# version1_1.net
KiCad netlist of a schematic drawn in EAGLE
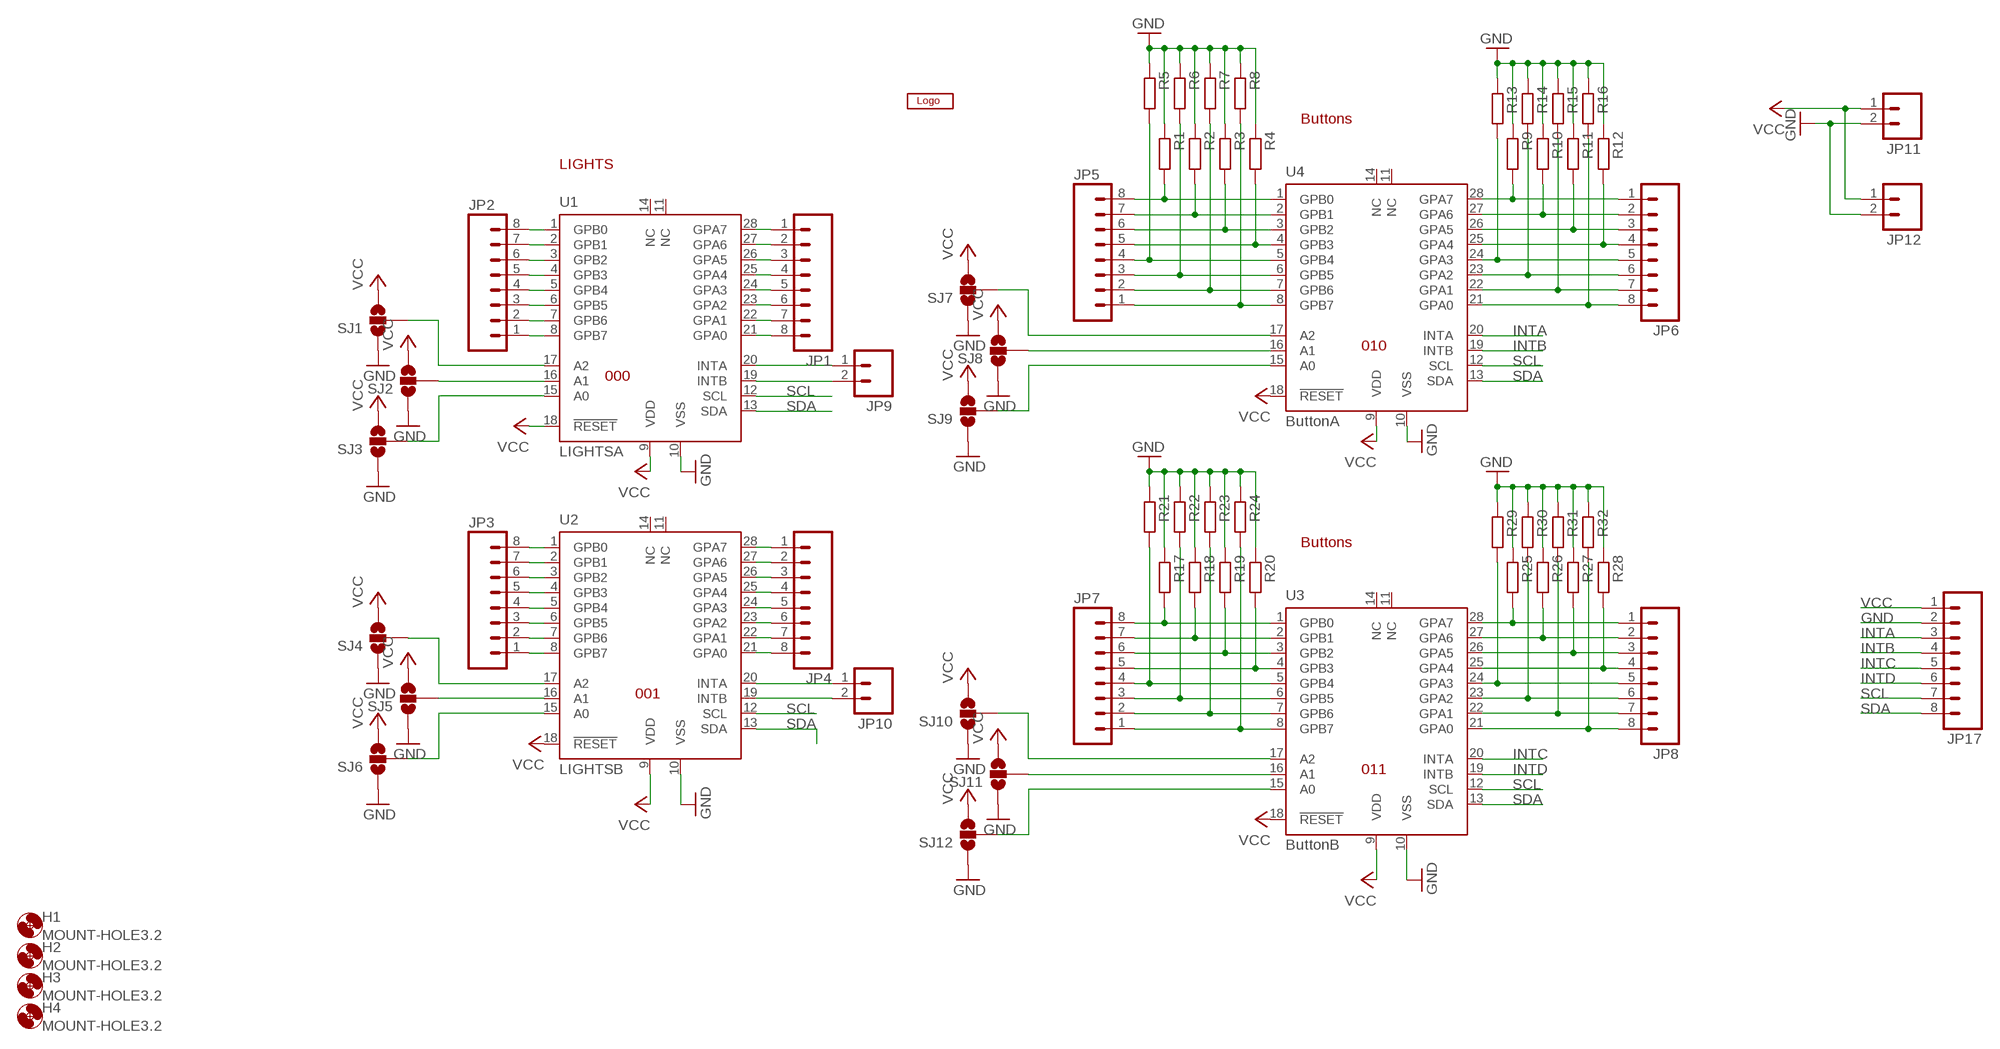
[diagram p0: schematic, sheet 1]

(export (version "E")
  (design (tool "Eeschema 10.0.6"))
  (components
    (comp (ref "H1")
      (value "MOUNT-HOLE3.2")
      (footprint "eagle-import:3,2")
      (libsource (lib "eagle-import") (part "MOUNT-HOLE3.2"))
    )
    (comp (ref "H2")
      (value "MOUNT-HOLE3.2")
      (footprint "eagle-import:3,2")
      (libsource (lib "eagle-import") (part "MOUNT-HOLE3.2"))
    )
    (comp (ref "H3")
      (value "MOUNT-HOLE3.2")
      (footprint "eagle-import:3,2")
      (libsource (lib "eagle-import") (part "MOUNT-HOLE3.2"))
    )
    (comp (ref "H4")
      (value "MOUNT-HOLE3.2")
      (footprint "eagle-import:3,2")
      (libsource (lib "eagle-import") (part "MOUNT-HOLE3.2"))
    )
    (comp (ref "JP1")
      (value "M08LOCK")
      (footprint "eagle-import:1X08_LOCK")
      (libsource (lib "eagle-import") (part "M08LOCK"))
    )
    (comp (ref "JP2")
      (value "M08LOCK")
      (footprint "eagle-import:1X08_LOCK")
      (libsource (lib "eagle-import") (part "M08LOCK"))
    )
    (comp (ref "JP3")
      (value "M08LOCK")
      (footprint "eagle-import:1X08_LOCK")
      (libsource (lib "eagle-import") (part "M08LOCK"))
    )
    (comp (ref "JP4")
      (value "M08LOCK")
      (footprint "eagle-import:1X08_LOCK")
      (libsource (lib "eagle-import") (part "M08LOCK"))
    )
    (comp (ref "JP5")
      (value "M08LOCK")
      (footprint "eagle-import:1X08_LOCK")
      (libsource (lib "eagle-import") (part "M08LOCK"))
    )
    (comp (ref "JP6")
      (value "M08LOCK")
      (footprint "eagle-import:1X08_LOCK")
      (libsource (lib "eagle-import") (part "M08LOCK"))
    )
    (comp (ref "JP7")
      (value "M08LOCK")
      (footprint "eagle-import:1X08_LOCK")
      (libsource (lib "eagle-import") (part "M08LOCK"))
    )
    (comp (ref "JP8")
      (value "M08LOCK")
      (footprint "eagle-import:1X08_LOCK")
      (libsource (lib "eagle-import") (part "M08LOCK"))
    )
    (comp (ref "JP9")
      (value "M021X02_NO_SILK")
      (footprint "eagle-import:1X02_NO_SILK")
      (libsource (lib "eagle-import") (part "M021X02_NO_SILK"))
    )
    (comp (ref "JP10")
      (value "M021X02_NO_SILK")
      (footprint "eagle-import:1X02_NO_SILK")
      (libsource (lib "eagle-import") (part "M021X02_NO_SILK"))
    )
    (comp (ref "JP11")
      (value "M021X02_NO_SILK")
      (footprint "eagle-import:1X02_NO_SILK")
      (libsource (lib "eagle-import") (part "M021X02_NO_SILK"))
    )
    (comp (ref "JP12")
      (value "M021X02_NO_SILK")
      (footprint "eagle-import:1X02_NO_SILK")
      (libsource (lib "eagle-import") (part "M021X02_NO_SILK"))
    )
    (comp (ref "JP17")
      (value "M08LOCK")
      (footprint "eagle-import:1X08_LOCK")
      (libsource (lib "eagle-import") (part "M08LOCK"))
    )
    (comp (ref "R1")
      (value "R-EU_R0805")
      (footprint "eagle-import:R0805")
      (libsource (lib "eagle-import") (part "R-EU_R0805"))
    )
    (comp (ref "R2")
      (value "R-EU_R0805")
      (footprint "eagle-import:R0805")
      (libsource (lib "eagle-import") (part "R-EU_R0805"))
    )
    (comp (ref "R3")
      (value "R-EU_R0805")
      (footprint "eagle-import:R0805")
      (libsource (lib "eagle-import") (part "R-EU_R0805"))
    )
    (comp (ref "R4")
      (value "R-EU_R0805")
      (footprint "eagle-import:R0805")
      (libsource (lib "eagle-import") (part "R-EU_R0805"))
    )
    (comp (ref "R5")
      (value "R-EU_R0805")
      (footprint "eagle-import:R0805")
      (libsource (lib "eagle-import") (part "R-EU_R0805"))
    )
    (comp (ref "R6")
      (value "R-EU_R0805")
      (footprint "eagle-import:R0805")
      (libsource (lib "eagle-import") (part "R-EU_R0805"))
    )
    (comp (ref "R7")
      (value "R-EU_R0805")
      (footprint "eagle-import:R0805")
      (libsource (lib "eagle-import") (part "R-EU_R0805"))
    )
    (comp (ref "R8")
      (value "R-EU_R0805")
      (footprint "eagle-import:R0805")
      (libsource (lib "eagle-import") (part "R-EU_R0805"))
    )
    (comp (ref "R9")
      (value "R-EU_R0805")
      (footprint "eagle-import:R0805")
      (libsource (lib "eagle-import") (part "R-EU_R0805"))
    )
    (comp (ref "R10")
      (value "R-EU_R0805")
      (footprint "eagle-import:R0805")
      (libsource (lib "eagle-import") (part "R-EU_R0805"))
    )
    (comp (ref "R11")
      (value "R-EU_R0805")
      (footprint "eagle-import:R0805")
      (libsource (lib "eagle-import") (part "R-EU_R0805"))
    )
    (comp (ref "R12")
      (value "R-EU_R0805")
      (footprint "eagle-import:R0805")
      (libsource (lib "eagle-import") (part "R-EU_R0805"))
    )
    (comp (ref "R13")
      (value "R-EU_R0805")
      (footprint "eagle-import:R0805")
      (libsource (lib "eagle-import") (part "R-EU_R0805"))
    )
    (comp (ref "R14")
      (value "R-EU_R0805")
      (footprint "eagle-import:R0805")
      (libsource (lib "eagle-import") (part "R-EU_R0805"))
    )
    (comp (ref "R15")
      (value "R-EU_R0805")
      (footprint "eagle-import:R0805")
      (libsource (lib "eagle-import") (part "R-EU_R0805"))
    )
    (comp (ref "R16")
      (value "R-EU_R0805")
      (footprint "eagle-import:R0805")
      (libsource (lib "eagle-import") (part "R-EU_R0805"))
    )
    (comp (ref "R17")
      (value "R-EU_R0805")
      (footprint "eagle-import:R0805")
      (libsource (lib "eagle-import") (part "R-EU_R0805"))
    )
    (comp (ref "R18")
      (value "R-EU_R0805")
      (footprint "eagle-import:R0805")
      (libsource (lib "eagle-import") (part "R-EU_R0805"))
    )
    (comp (ref "R19")
      (value "R-EU_R0805")
      (footprint "eagle-import:R0805")
      (libsource (lib "eagle-import") (part "R-EU_R0805"))
    )
    (comp (ref "R20")
      (value "R-EU_R0805")
      (footprint "eagle-import:R0805")
      (libsource (lib "eagle-import") (part "R-EU_R0805"))
    )
    (comp (ref "R21")
      (value "R-EU_R0805")
      (footprint "eagle-import:R0805")
      (libsource (lib "eagle-import") (part "R-EU_R0805"))
    )
    (comp (ref "R22")
      (value "R-EU_R0805")
      (footprint "eagle-import:R0805")
      (libsource (lib "eagle-import") (part "R-EU_R0805"))
    )
    (comp (ref "R23")
      (value "R-EU_R0805")
      (footprint "eagle-import:R0805")
      (libsource (lib "eagle-import") (part "R-EU_R0805"))
    )
    (comp (ref "R24")
      (value "R-EU_R0805")
      (footprint "eagle-import:R0805")
      (libsource (lib "eagle-import") (part "R-EU_R0805"))
    )
    (comp (ref "R25")
      (value "R-EU_R0805")
      (footprint "eagle-import:R0805")
      (libsource (lib "eagle-import") (part "R-EU_R0805"))
    )
    (comp (ref "R26")
      (value "R-EU_R0805")
      (footprint "eagle-import:R0805")
      (libsource (lib "eagle-import") (part "R-EU_R0805"))
    )
    (comp (ref "R27")
      (value "R-EU_R0805")
      (footprint "eagle-import:R0805")
      (libsource (lib "eagle-import") (part "R-EU_R0805"))
    )
    (comp (ref "R28")
      (value "R-EU_R0805")
      (footprint "eagle-import:R0805")
      (libsource (lib "eagle-import") (part "R-EU_R0805"))
    )
    (comp (ref "R29")
      (value "R-EU_R0805")
      (footprint "eagle-import:R0805")
      (libsource (lib "eagle-import") (part "R-EU_R0805"))
    )
    (comp (ref "R30")
      (value "R-EU_R0805")
      (footprint "eagle-import:R0805")
      (libsource (lib "eagle-import") (part "R-EU_R0805"))
    )
    (comp (ref "R31")
      (value "R-EU_R0805")
      (footprint "eagle-import:R0805")
      (libsource (lib "eagle-import") (part "R-EU_R0805"))
    )
    (comp (ref "R32")
      (value "R-EU_R0805")
      (footprint "eagle-import:R0805")
      (libsource (lib "eagle-import") (part "R-EU_R0805"))
    )
    (comp (ref "SJ1")
      (value "SOLDERJUMPER_2WAY-OLDS")
      (footprint "eagle-import:SJ_3")
      (libsource (lib "eagle-import") (part "SOLDERJUMPER_2WAY-OLDS"))
    )
    (comp (ref "SJ2")
      (value "SOLDERJUMPER_2WAY-OLDS")
      (footprint "eagle-import:SJ_3")
      (libsource (lib "eagle-import") (part "SOLDERJUMPER_2WAY-OLDS"))
    )
    (comp (ref "SJ3")
      (value "SOLDERJUMPER_2WAY-OLDS")
      (footprint "eagle-import:SJ_3")
      (libsource (lib "eagle-import") (part "SOLDERJUMPER_2WAY-OLDS"))
    )
    (comp (ref "SJ4")
      (value "SOLDERJUMPER_2WAY-OLDS")
      (footprint "eagle-import:SJ_3")
      (libsource (lib "eagle-import") (part "SOLDERJUMPER_2WAY-OLDS"))
    )
    (comp (ref "SJ5")
      (value "SOLDERJUMPER_2WAY-OLDS")
      (footprint "eagle-import:SJ_3")
      (libsource (lib "eagle-import") (part "SOLDERJUMPER_2WAY-OLDS"))
    )
    (comp (ref "SJ6")
      (value "SOLDERJUMPER_2WAY-OLDS")
      (footprint "eagle-import:SJ_3")
      (libsource (lib "eagle-import") (part "SOLDERJUMPER_2WAY-OLDS"))
    )
    (comp (ref "SJ7")
      (value "SOLDERJUMPER_2WAY-OLDS")
      (footprint "eagle-import:SJ_3")
      (libsource (lib "eagle-import") (part "SOLDERJUMPER_2WAY-OLDS"))
    )
    (comp (ref "SJ8")
      (value "SOLDERJUMPER_2WAY-OLDS")
      (footprint "eagle-import:SJ_3")
      (libsource (lib "eagle-import") (part "SOLDERJUMPER_2WAY-OLDS"))
    )
    (comp (ref "SJ9")
      (value "SOLDERJUMPER_2WAY-OLDS")
      (footprint "eagle-import:SJ_3")
      (libsource (lib "eagle-import") (part "SOLDERJUMPER_2WAY-OLDS"))
    )
    (comp (ref "SJ10")
      (value "SOLDERJUMPER_2WAY-OLDS")
      (footprint "eagle-import:SJ_3")
      (libsource (lib "eagle-import") (part "SOLDERJUMPER_2WAY-OLDS"))
    )
    (comp (ref "SJ11")
      (value "SOLDERJUMPER_2WAY-OLDS")
      (footprint "eagle-import:SJ_3")
      (libsource (lib "eagle-import") (part "SOLDERJUMPER_2WAY-OLDS"))
    )
    (comp (ref "SJ12")
      (value "SOLDERJUMPER_2WAY-OLDS")
      (footprint "eagle-import:SJ_3")
      (libsource (lib "eagle-import") (part "SOLDERJUMPER_2WAY-OLDS"))
    )
    (comp (ref "U$1")
      (value "BUNNYLOGOCALVIN2")
      (footprint "eagle-import:CALVIN2")
      (libsource (lib "eagle-import") (part "BUNNYLOGOCALVIN2"))
    )
    (comp (ref "U1")
      (value "LIGHTSA")
      (footprint "eagle-import:MCP23017A")
      (libsource (lib "eagle-import") (part "MCP23017A"))
    )
    (comp (ref "U2")
      (value "LIGHTSB")
      (footprint "eagle-import:MCP23017A")
      (libsource (lib "eagle-import") (part "MCP23017A"))
    )
    (comp (ref "U3")
      (value "ButtonB")
      (footprint "eagle-import:MCP23017A")
      (libsource (lib "eagle-import") (part "MCP23017A"))
    )
    (comp (ref "U4")
      (value "ButtonA")
      (footprint "eagle-import:MCP23017A")
      (libsource (lib "eagle-import") (part "MCP23017A"))
    )
  )
  (nets
    (net (code "1") (name "/INTA") (class "Default")
      (node (ref "JP17") (pin "3") (pinfunction "3_3") (pintype "passive"))
      (node (ref "U4") (pin "20") (pinfunction "INTA_20") (pintype "bidirectional"))
    )
    (net (code "2") (name "/INTB") (class "Default")
      (node (ref "JP17") (pin "4") (pinfunction "4_4") (pintype "passive"))
      (node (ref "U4") (pin "19") (pinfunction "INTB_19") (pintype "bidirectional"))
    )
    (net (code "3") (name "/INTC") (class "Default")
      (node (ref "JP17") (pin "5") (pinfunction "5_5") (pintype "passive"))
      (node (ref "U3") (pin "20") (pinfunction "INTA_20") (pintype "bidirectional"))
    )
    (net (code "4") (name "/INTD") (class "Default")
      (node (ref "JP17") (pin "6") (pinfunction "6_6") (pintype "passive"))
      (node (ref "U3") (pin "19") (pinfunction "INTB_19") (pintype "bidirectional"))
    )
    (net (code "5") (name "/SCL") (class "Default")
      (node (ref "JP17") (pin "7") (pinfunction "7_7") (pintype "passive"))
      (node (ref "U1") (pin "12") (pinfunction "SCL_12") (pintype "bidirectional"))
      (node (ref "U2") (pin "12") (pinfunction "SCL_12") (pintype "bidirectional"))
      (node (ref "U3") (pin "12") (pinfunction "SCL_12") (pintype "bidirectional"))
      (node (ref "U4") (pin "12") (pinfunction "SCL_12") (pintype "bidirectional"))
    )
    (net (code "6") (name "/SDA") (class "Default")
      (node (ref "JP17") (pin "8") (pinfunction "8_8") (pintype "passive"))
      (node (ref "U1") (pin "13") (pinfunction "SDA_13") (pintype "bidirectional"))
      (node (ref "U2") (pin "13") (pinfunction "SDA_13") (pintype "bidirectional"))
      (node (ref "U3") (pin "13") (pinfunction "SDA_13") (pintype "bidirectional"))
      (node (ref "U4") (pin "13") (pinfunction "SDA_13") (pintype "bidirectional"))
    )
    (net (code "7") (name "GND") (class "Default")
      (node (ref "JP11") (pin "2") (pinfunction "2_2") (pintype "passive"))
      (node (ref "JP12") (pin "2") (pinfunction "2_2") (pintype "passive"))
      (node (ref "JP17") (pin "2") (pinfunction "2_2") (pintype "passive"))
      (node (ref "R1") (pin "1") (pinfunction "1_1") (pintype "passive"))
      (node (ref "R10") (pin "1") (pinfunction "1_1") (pintype "passive"))
      (node (ref "R11") (pin "1") (pinfunction "1_1") (pintype "passive"))
      (node (ref "R12") (pin "1") (pinfunction "1_1") (pintype "passive"))
      (node (ref "R13") (pin "1") (pinfunction "1_1") (pintype "passive"))
      (node (ref "R14") (pin "1") (pinfunction "1_1") (pintype "passive"))
      (node (ref "R15") (pin "1") (pinfunction "1_1") (pintype "passive"))
      (node (ref "R16") (pin "1") (pinfunction "1_1") (pintype "passive"))
      (node (ref "R17") (pin "1") (pinfunction "1_1") (pintype "passive"))
      (node (ref "R18") (pin "1") (pinfunction "1_1") (pintype "passive"))
      (node (ref "R19") (pin "1") (pinfunction "1_1") (pintype "passive"))
      (node (ref "R2") (pin "1") (pinfunction "1_1") (pintype "passive"))
      (node (ref "R20") (pin "1") (pinfunction "1_1") (pintype "passive"))
      (node (ref "R21") (pin "1") (pinfunction "1_1") (pintype "passive"))
      (node (ref "R22") (pin "1") (pinfunction "1_1") (pintype "passive"))
      (node (ref "R23") (pin "1") (pinfunction "1_1") (pintype "passive"))
      (node (ref "R24") (pin "1") (pinfunction "1_1") (pintype "passive"))
      (node (ref "R25") (pin "1") (pinfunction "1_1") (pintype "passive"))
      (node (ref "R26") (pin "1") (pinfunction "1_1") (pintype "passive"))
      (node (ref "R27") (pin "1") (pinfunction "1_1") (pintype "passive"))
      (node (ref "R28") (pin "1") (pinfunction "1_1") (pintype "passive"))
      (node (ref "R29") (pin "1") (pinfunction "1_1") (pintype "passive"))
      (node (ref "R3") (pin "1") (pinfunction "1_1") (pintype "passive"))
      (node (ref "R30") (pin "1") (pinfunction "1_1") (pintype "passive"))
      (node (ref "R31") (pin "1") (pinfunction "1_1") (pintype "passive"))
      (node (ref "R32") (pin "1") (pinfunction "1_1") (pintype "passive"))
      (node (ref "R4") (pin "1") (pinfunction "1_1") (pintype "passive"))
      (node (ref "R5") (pin "1") (pinfunction "1_1") (pintype "passive"))
      (node (ref "R6") (pin "1") (pinfunction "1_1") (pintype "passive"))
      (node (ref "R7") (pin "1") (pinfunction "1_1") (pintype "passive"))
      (node (ref "R8") (pin "1") (pinfunction "1_1") (pintype "passive"))
      (node (ref "R9") (pin "1") (pinfunction "1_1") (pintype "passive"))
      (node (ref "SJ1") (pin "1") (pinfunction "1_1") (pintype "passive"))
      (node (ref "SJ10") (pin "1") (pinfunction "1_1") (pintype "passive"))
      (node (ref "SJ11") (pin "1") (pinfunction "1_1") (pintype "passive"))
      (node (ref "SJ12") (pin "1") (pinfunction "1_1") (pintype "passive"))
      (node (ref "SJ2") (pin "1") (pinfunction "1_1") (pintype "passive"))
      (node (ref "SJ3") (pin "1") (pinfunction "1_1") (pintype "passive"))
      (node (ref "SJ4") (pin "1") (pinfunction "1_1") (pintype "passive"))
      (node (ref "SJ5") (pin "1") (pinfunction "1_1") (pintype "passive"))
      (node (ref "SJ6") (pin "1") (pinfunction "1_1") (pintype "passive"))
      (node (ref "SJ7") (pin "1") (pinfunction "1_1") (pintype "passive"))
      (node (ref "SJ8") (pin "1") (pinfunction "1_1") (pintype "passive"))
      (node (ref "SJ9") (pin "1") (pinfunction "1_1") (pintype "passive"))
      (node (ref "U1") (pin "10") (pinfunction "VSS_10") (pintype "power_in"))
      (node (ref "U2") (pin "10") (pinfunction "VSS_10") (pintype "power_in"))
      (node (ref "U3") (pin "10") (pinfunction "VSS_10") (pintype "power_in"))
      (node (ref "U4") (pin "10") (pinfunction "VSS_10") (pintype "power_in"))
    )
    (net (code "8") (name "Net-(U1-A0)") (class "Default")
      (node (ref "SJ3") (pin "2") (pinfunction "2_2") (pintype "passive"))
      (node (ref "U1") (pin "15") (pinfunction "A0_15") (pintype "bidirectional"))
    )
    (net (code "9") (name "Net-(U1-A1)") (class "Default")
      (node (ref "SJ2") (pin "2") (pinfunction "2_2") (pintype "passive"))
      (node (ref "U1") (pin "16") (pinfunction "A1_16") (pintype "bidirectional"))
    )
    (net (code "10") (name "Net-(U1-A2)") (class "Default")
      (node (ref "SJ1") (pin "2") (pinfunction "2_2") (pintype "passive"))
      (node (ref "U1") (pin "17") (pinfunction "A2_17") (pintype "bidirectional"))
    )
    (net (code "11") (name "Net-(U1-GPA0)") (class "Default")
      (node (ref "JP1") (pin "8") (pinfunction "8_8") (pintype "passive"))
      (node (ref "U1") (pin "21") (pinfunction "GPA0_21") (pintype "bidirectional"))
    )
    (net (code "12") (name "Net-(U1-GPA1)") (class "Default")
      (node (ref "JP1") (pin "7") (pinfunction "7_7") (pintype "passive"))
      (node (ref "U1") (pin "22") (pinfunction "GPA1_22") (pintype "bidirectional"))
    )
    (net (code "13") (name "Net-(U1-GPA2)") (class "Default")
      (node (ref "JP1") (pin "6") (pinfunction "6_6") (pintype "passive"))
      (node (ref "U1") (pin "23") (pinfunction "GPA2_23") (pintype "bidirectional"))
    )
    (net (code "14") (name "Net-(U1-GPA3)") (class "Default")
      (node (ref "JP1") (pin "5") (pinfunction "5_5") (pintype "passive"))
      (node (ref "U1") (pin "24") (pinfunction "GPA3_24") (pintype "bidirectional"))
    )
    (net (code "15") (name "Net-(U1-GPA4)") (class "Default")
      (node (ref "JP1") (pin "4") (pinfunction "4_4") (pintype "passive"))
      (node (ref "U1") (pin "25") (pinfunction "GPA4_25") (pintype "bidirectional"))
    )
    (net (code "16") (name "Net-(U1-GPA5)") (class "Default")
      (node (ref "JP1") (pin "3") (pinfunction "3_3") (pintype "passive"))
      (node (ref "U1") (pin "26") (pinfunction "GPA5_26") (pintype "bidirectional"))
    )
    (net (code "17") (name "Net-(U1-GPA6)") (class "Default")
      (node (ref "JP1") (pin "2") (pinfunction "2_2") (pintype "passive"))
      (node (ref "U1") (pin "27") (pinfunction "GPA6_27") (pintype "bidirectional"))
    )
    (net (code "18") (name "Net-(U1-GPA7)") (class "Default")
      (node (ref "JP1") (pin "1") (pinfunction "1_1") (pintype "passive"))
      (node (ref "U1") (pin "28") (pinfunction "GPA7_28") (pintype "bidirectional"))
    )
    (net (code "19") (name "Net-(U1-GPB0)") (class "Default")
      (node (ref "JP2") (pin "8") (pinfunction "8_8") (pintype "passive"))
      (node (ref "U1") (pin "1") (pinfunction "GPB0_1") (pintype "bidirectional"))
    )
    (net (code "20") (name "Net-(U1-GPB1)") (class "Default")
      (node (ref "JP2") (pin "7") (pinfunction "7_7") (pintype "passive"))
      (node (ref "U1") (pin "2") (pinfunction "GPB1_2") (pintype "bidirectional"))
    )
    (net (code "21") (name "Net-(U1-GPB2)") (class "Default")
      (node (ref "JP2") (pin "6") (pinfunction "6_6") (pintype "passive"))
      (node (ref "U1") (pin "3") (pinfunction "GPB2_3") (pintype "bidirectional"))
    )
    (net (code "22") (name "Net-(U1-GPB3)") (class "Default")
      (node (ref "JP2") (pin "5") (pinfunction "5_5") (pintype "passive"))
      (node (ref "U1") (pin "4") (pinfunction "GPB3_4") (pintype "bidirectional"))
    )
    (net (code "23") (name "Net-(U1-GPB4)") (class "Default")
      (node (ref "JP2") (pin "4") (pinfunction "4_4") (pintype "passive"))
      (node (ref "U1") (pin "5") (pinfunction "GPB4_5") (pintype "bidirectional"))
    )
    (net (code "24") (name "Net-(U1-GPB5)") (class "Default")
      (node (ref "JP2") (pin "3") (pinfunction "3_3") (pintype "passive"))
      (node (ref "U1") (pin "6") (pinfunction "GPB5_6") (pintype "bidirectional"))
    )
    (net (code "25") (name "Net-(U1-GPB6)") (class "Default")
      (node (ref "JP2") (pin "2") (pinfunction "2_2") (pintype "passive"))
      (node (ref "U1") (pin "7") (pinfunction "GPB6_7") (pintype "bidirectional"))
    )
    (net (code "26") (name "Net-(U1-GPB7)") (class "Default")
      (node (ref "JP2") (pin "1") (pinfunction "1_1") (pintype "passive"))
      (node (ref "U1") (pin "8") (pinfunction "GPB7_8") (pintype "bidirectional"))
    )
    (net (code "27") (name "Net-(U1-INTA)") (class "Default")
      (node (ref "JP9") (pin "1") (pinfunction "1_1") (pintype "passive"))
      (node (ref "U1") (pin "20") (pinfunction "INTA_20") (pintype "bidirectional"))
    )
    (net (code "28") (name "Net-(U1-INTB)") (class "Default")
      (node (ref "JP9") (pin "2") (pinfunction "2_2") (pintype "passive"))
      (node (ref "U1") (pin "19") (pinfunction "INTB_19") (pintype "bidirectional"))
    )
    (net (code "29") (name "Net-(U2-A0)") (class "Default")
      (node (ref "SJ6") (pin "2") (pinfunction "2_2") (pintype "passive"))
      (node (ref "U2") (pin "15") (pinfunction "A0_15") (pintype "bidirectional"))
    )
    (net (code "30") (name "Net-(U2-A1)") (class "Default")
      (node (ref "SJ5") (pin "2") (pinfunction "2_2") (pintype "passive"))
      (node (ref "U2") (pin "16") (pinfunction "A1_16") (pintype "bidirectional"))
    )
    (net (code "31") (name "Net-(U2-A2)") (class "Default")
      (node (ref "SJ4") (pin "2") (pinfunction "2_2") (pintype "passive"))
      (node (ref "U2") (pin "17") (pinfunction "A2_17") (pintype "bidirectional"))
    )
    (net (code "32") (name "Net-(U2-GPA0)") (class "Default")
      (node (ref "JP4") (pin "8") (pinfunction "8_8") (pintype "passive"))
      (node (ref "U2") (pin "21") (pinfunction "GPA0_21") (pintype "bidirectional"))
    )
    (net (code "33") (name "Net-(U2-GPA1)") (class "Default")
      (node (ref "JP4") (pin "7") (pinfunction "7_7") (pintype "passive"))
      (node (ref "U2") (pin "22") (pinfunction "GPA1_22") (pintype "bidirectional"))
    )
    (net (code "34") (name "Net-(U2-GPA2)") (class "Default")
      (node (ref "JP4") (pin "6") (pinfunction "6_6") (pintype "passive"))
      (node (ref "U2") (pin "23") (pinfunction "GPA2_23") (pintype "bidirectional"))
    )
    (net (code "35") (name "Net-(U2-GPA3)") (class "Default")
      (node (ref "JP4") (pin "5") (pinfunction "5_5") (pintype "passive"))
      (node (ref "U2") (pin "24") (pinfunction "GPA3_24") (pintype "bidirectional"))
    )
    (net (code "36") (name "Net-(U2-GPA4)") (class "Default")
      (node (ref "JP4") (pin "4") (pinfunction "4_4") (pintype "passive"))
      (node (ref "U2") (pin "25") (pinfunction "GPA4_25") (pintype "bidirectional"))
    )
    (net (code "37") (name "Net-(U2-GPA5)") (class "Default")
      (node (ref "JP4") (pin "3") (pinfunction "3_3") (pintype "passive"))
      (node (ref "U2") (pin "26") (pinfunction "GPA5_26") (pintype "bidirectional"))
    )
    (net (code "38") (name "Net-(U2-GPA6)") (class "Default")
      (node (ref "JP4") (pin "2") (pinfunction "2_2") (pintype "passive"))
      (node (ref "U2") (pin "27") (pinfunction "GPA6_27") (pintype "bidirectional"))
    )
    (net (code "39") (name "Net-(U2-GPA7)") (class "Default")
      (node (ref "JP4") (pin "1") (pinfunction "1_1") (pintype "passive"))
      (node (ref "U2") (pin "28") (pinfunction "GPA7_28") (pintype "bidirectional"))
    )
    (net (code "40") (name "Net-(U2-GPB0)") (class "Default")
      (node (ref "JP3") (pin "8") (pinfunction "8_8") (pintype "passive"))
      (node (ref "U2") (pin "1") (pinfunction "GPB0_1") (pintype "bidirectional"))
    )
    (net (code "41") (name "Net-(U2-GPB1)") (class "Default")
      (node (ref "JP3") (pin "7") (pinfunction "7_7") (pintype "passive"))
      (node (ref "U2") (pin "2") (pinfunction "GPB1_2") (pintype "bidirectional"))
    )
    (net (code "42") (name "Net-(U2-GPB2)") (class "Default")
      (node (ref "JP3") (pin "6") (pinfunction "6_6") (pintype "passive"))
      (node (ref "U2") (pin "3") (pinfunction "GPB2_3") (pintype "bidirectional"))
    )
    (net (code "43") (name "Net-(U2-GPB3)") (class "Default")
      (node (ref "JP3") (pin "5") (pinfunction "5_5") (pintype "passive"))
      (node (ref "U2") (pin "4") (pinfunction "GPB3_4") (pintype "bidirectional"))
    )
    (net (code "44") (name "Net-(U2-GPB4)") (class "Default")
      (node (ref "JP3") (pin "4") (pinfunction "4_4") (pintype "passive"))
      (node (ref "U2") (pin "5") (pinfunction "GPB4_5") (pintype "bidirectional"))
    )
    (net (code "45") (name "Net-(U2-GPB5)") (class "Default")
      (node (ref "JP3") (pin "3") (pinfunction "3_3") (pintype "passive"))
      (node (ref "U2") (pin "6") (pinfunction "GPB5_6") (pintype "bidirectional"))
    )
    (net (code "46") (name "Net-(U2-GPB6)") (class "Default")
      (node (ref "JP3") (pin "2") (pinfunction "2_2") (pintype "passive"))
      (node (ref "U2") (pin "7") (pinfunction "GPB6_7") (pintype "bidirectional"))
    )
    (net (code "47") (name "Net-(U2-GPB7)") (class "Default")
      (node (ref "JP3") (pin "1") (pinfunction "1_1") (pintype "passive"))
      (node (ref "U2") (pin "8") (pinfunction "GPB7_8") (pintype "bidirectional"))
    )
    (net (code "48") (name "Net-(U2-INTA)") (class "Default")
      (node (ref "JP10") (pin "1") (pinfunction "1_1") (pintype "passive"))
      (node (ref "U2") (pin "20") (pinfunction "INTA_20") (pintype "bidirectional"))
    )
    (net (code "49") (name "Net-(U2-INTB)") (class "Default")
      (node (ref "JP10") (pin "2") (pinfunction "2_2") (pintype "passive"))
      (node (ref "U2") (pin "19") (pinfunction "INTB_19") (pintype "bidirectional"))
    )
    (net (code "50") (name "Net-(U3-A0)") (class "Default")
      (node (ref "SJ12") (pin "2") (pinfunction "2_2") (pintype "passive"))
      (node (ref "U3") (pin "15") (pinfunction "A0_15") (pintype "bidirectional"))
    )
    (net (code "51") (name "Net-(U3-A1)") (class "Default")
      (node (ref "SJ11") (pin "2") (pinfunction "2_2") (pintype "passive"))
      (node (ref "U3") (pin "16") (pinfunction "A1_16") (pintype "bidirectional"))
    )
    (net (code "52") (name "Net-(U3-A2)") (class "Default")
      (node (ref "SJ10") (pin "2") (pinfunction "2_2") (pintype "passive"))
      (node (ref "U3") (pin "17") (pinfunction "A2_17") (pintype "bidirectional"))
    )
    (net (code "53") (name "Net-(U3-GPA0)") (class "Default")
      (node (ref "JP8") (pin "8") (pinfunction "8_8") (pintype "passive"))
      (node (ref "R32") (pin "2") (pinfunction "2_2") (pintype "passive"))
      (node (ref "U3") (pin "21") (pinfunction "GPA0_21") (pintype "bidirectional"))
    )
    (net (code "54") (name "Net-(U3-GPA1)") (class "Default")
      (node (ref "JP8") (pin "7") (pinfunction "7_7") (pintype "passive"))
      (node (ref "R31") (pin "2") (pinfunction "2_2") (pintype "passive"))
      (node (ref "U3") (pin "22") (pinfunction "GPA1_22") (pintype "bidirectional"))
    )
    (net (code "55") (name "Net-(U3-GPA2)") (class "Default")
      (node (ref "JP8") (pin "6") (pinfunction "6_6") (pintype "passive"))
      (node (ref "R30") (pin "2") (pinfunction "2_2") (pintype "passive"))
      (node (ref "U3") (pin "23") (pinfunction "GPA2_23") (pintype "bidirectional"))
    )
    (net (code "56") (name "Net-(U3-GPA3)") (class "Default")
      (node (ref "JP8") (pin "5") (pinfunction "5_5") (pintype "passive"))
      (node (ref "R29") (pin "2") (pinfunction "2_2") (pintype "passive"))
      (node (ref "U3") (pin "24") (pinfunction "GPA3_24") (pintype "bidirectional"))
    )
    (net (code "57") (name "Net-(U3-GPA4)") (class "Default")
      (node (ref "JP8") (pin "4") (pinfunction "4_4") (pintype "passive"))
      (node (ref "R28") (pin "2") (pinfunction "2_2") (pintype "passive"))
      (node (ref "U3") (pin "25") (pinfunction "GPA4_25") (pintype "bidirectional"))
    )
    (net (code "58") (name "Net-(U3-GPA5)") (class "Default")
      (node (ref "JP8") (pin "3") (pinfunction "3_3") (pintype "passive"))
      (node (ref "R27") (pin "2") (pinfunction "2_2") (pintype "passive"))
      (node (ref "U3") (pin "26") (pinfunction "GPA5_26") (pintype "bidirectional"))
    )
    (net (code "59") (name "Net-(U3-GPA6)") (class "Default")
      (node (ref "JP8") (pin "2") (pinfunction "2_2") (pintype "passive"))
      (node (ref "R26") (pin "2") (pinfunction "2_2") (pintype "passive"))
      (node (ref "U3") (pin "27") (pinfunction "GPA6_27") (pintype "bidirectional"))
    )
    (net (code "60") (name "Net-(U3-GPA7)") (class "Default")
      (node (ref "JP8") (pin "1") (pinfunction "1_1") (pintype "passive"))
      (node (ref "R25") (pin "2") (pinfunction "2_2") (pintype "passive"))
      (node (ref "U3") (pin "28") (pinfunction "GPA7_28") (pintype "bidirectional"))
    )
    (net (code "61") (name "Net-(U3-GPB0)") (class "Default")
      (node (ref "JP7") (pin "8") (pinfunction "8_8") (pintype "passive"))
      (node (ref "R17") (pin "2") (pinfunction "2_2") (pintype "passive"))
      (node (ref "U3") (pin "1") (pinfunction "GPB0_1") (pintype "bidirectional"))
    )
    (net (code "62") (name "Net-(U3-GPB1)") (class "Default")
      (node (ref "JP7") (pin "7") (pinfunction "7_7") (pintype "passive"))
      (node (ref "R18") (pin "2") (pinfunction "2_2") (pintype "passive"))
      (node (ref "U3") (pin "2") (pinfunction "GPB1_2") (pintype "bidirectional"))
    )
    (net (code "63") (name "Net-(U3-GPB2)") (class "Default")
      (node (ref "JP7") (pin "6") (pinfunction "6_6") (pintype "passive"))
      (node (ref "R19") (pin "2") (pinfunction "2_2") (pintype "passive"))
      (node (ref "U3") (pin "3") (pinfunction "GPB2_3") (pintype "bidirectional"))
    )
    (net (code "64") (name "Net-(U3-GPB3)") (class "Default")
      (node (ref "JP7") (pin "5") (pinfunction "5_5") (pintype "passive"))
      (node (ref "R20") (pin "2") (pinfunction "2_2") (pintype "passive"))
      (node (ref "U3") (pin "4") (pinfunction "GPB3_4") (pintype "bidirectional"))
    )
    (net (code "65") (name "Net-(U3-GPB4)") (class "Default")
      (node (ref "JP7") (pin "4") (pinfunction "4_4") (pintype "passive"))
      (node (ref "R21") (pin "2") (pinfunction "2_2") (pintype "passive"))
      (node (ref "U3") (pin "5") (pinfunction "GPB4_5") (pintype "bidirectional"))
    )
    (net (code "66") (name "Net-(U3-GPB5)") (class "Default")
      (node (ref "JP7") (pin "3") (pinfunction "3_3") (pintype "passive"))
      (node (ref "R22") (pin "2") (pinfunction "2_2") (pintype "passive"))
      (node (ref "U3") (pin "6") (pinfunction "GPB5_6") (pintype "bidirectional"))
    )
    (net (code "67") (name "Net-(U3-GPB6)") (class "Default")
      (node (ref "JP7") (pin "2") (pinfunction "2_2") (pintype "passive"))
      (node (ref "R23") (pin "2") (pinfunction "2_2") (pintype "passive"))
      (node (ref "U3") (pin "7") (pinfunction "GPB6_7") (pintype "bidirectional"))
    )
    (net (code "68") (name "Net-(U3-GPB7)") (class "Default")
      (node (ref "JP7") (pin "1") (pinfunction "1_1") (pintype "passive"))
      (node (ref "R24") (pin "2") (pinfunction "2_2") (pintype "passive"))
      (node (ref "U3") (pin "8") (pinfunction "GPB7_8") (pintype "bidirectional"))
    )
    (net (code "69") (name "Net-(U4-A0)") (class "Default")
      (node (ref "SJ9") (pin "2") (pinfunction "2_2") (pintype "passive"))
      (node (ref "U4") (pin "15") (pinfunction "A0_15") (pintype "bidirectional"))
    )
    (net (code "70") (name "Net-(U4-A1)") (class "Default")
      (node (ref "SJ8") (pin "2") (pinfunction "2_2") (pintype "passive"))
      (node (ref "U4") (pin "16") (pinfunction "A1_16") (pintype "bidirectional"))
    )
    (net (code "71") (name "Net-(U4-A2)") (class "Default")
      (node (ref "SJ7") (pin "2") (pinfunction "2_2") (pintype "passive"))
      (node (ref "U4") (pin "17") (pinfunction "A2_17") (pintype "bidirectional"))
    )
    (net (code "72") (name "Net-(U4-GPA0)") (class "Default")
      (node (ref "JP6") (pin "8") (pinfunction "8_8") (pintype "passive"))
      (node (ref "R16") (pin "2") (pinfunction "2_2") (pintype "passive"))
      (node (ref "U4") (pin "21") (pinfunction "GPA0_21") (pintype "bidirectional"))
    )
    (net (code "73") (name "Net-(U4-GPA1)") (class "Default")
      (node (ref "JP6") (pin "7") (pinfunction "7_7") (pintype "passive"))
      (node (ref "R15") (pin "2") (pinfunction "2_2") (pintype "passive"))
      (node (ref "U4") (pin "22") (pinfunction "GPA1_22") (pintype "bidirectional"))
    )
    (net (code "74") (name "Net-(U4-GPA2)") (class "Default")
      (node (ref "JP6") (pin "6") (pinfunction "6_6") (pintype "passive"))
      (node (ref "R14") (pin "2") (pinfunction "2_2") (pintype "passive"))
      (node (ref "U4") (pin "23") (pinfunction "GPA2_23") (pintype "bidirectional"))
    )
    (net (code "75") (name "Net-(U4-GPA3)") (class "Default")
      (node (ref "JP6") (pin "5") (pinfunction "5_5") (pintype "passive"))
      (node (ref "R13") (pin "2") (pinfunction "2_2") (pintype "passive"))
      (node (ref "U4") (pin "24") (pinfunction "GPA3_24") (pintype "bidirectional"))
    )
    (net (code "76") (name "Net-(U4-GPA4)") (class "Default")
      (node (ref "JP6") (pin "4") (pinfunction "4_4") (pintype "passive"))
      (node (ref "R12") (pin "2") (pinfunction "2_2") (pintype "passive"))
      (node (ref "U4") (pin "25") (pinfunction "GPA4_25") (pintype "bidirectional"))
    )
    (net (code "77") (name "Net-(U4-GPA5)") (class "Default")
      (node (ref "JP6") (pin "3") (pinfunction "3_3") (pintype "passive"))
      (node (ref "R11") (pin "2") (pinfunction "2_2") (pintype "passive"))
      (node (ref "U4") (pin "26") (pinfunction "GPA5_26") (pintype "bidirectional"))
    )
    (net (code "78") (name "Net-(U4-GPA6)") (class "Default")
      (node (ref "JP6") (pin "2") (pinfunction "2_2") (pintype "passive"))
      (node (ref "R10") (pin "2") (pinfunction "2_2") (pintype "passive"))
      (node (ref "U4") (pin "27") (pinfunction "GPA6_27") (pintype "bidirectional"))
    )
    (net (code "79") (name "Net-(U4-GPA7)") (class "Default")
      (node (ref "JP6") (pin "1") (pinfunction "1_1") (pintype "passive"))
      (node (ref "R9") (pin "2") (pinfunction "2_2") (pintype "passive"))
      (node (ref "U4") (pin "28") (pinfunction "GPA7_28") (pintype "bidirectional"))
    )
    (net (code "80") (name "Net-(U4-GPB0)") (class "Default")
      (node (ref "JP5") (pin "8") (pinfunction "8_8") (pintype "passive"))
      (node (ref "R1") (pin "2") (pinfunction "2_2") (pintype "passive"))
      (node (ref "U4") (pin "1") (pinfunction "GPB0_1") (pintype "bidirectional"))
    )
    (net (code "81") (name "Net-(U4-GPB1)") (class "Default")
      (node (ref "JP5") (pin "7") (pinfunction "7_7") (pintype "passive"))
      (node (ref "R2") (pin "2") (pinfunction "2_2") (pintype "passive"))
      (node (ref "U4") (pin "2") (pinfunction "GPB1_2") (pintype "bidirectional"))
    )
    (net (code "82") (name "Net-(U4-GPB2)") (class "Default")
      (node (ref "JP5") (pin "6") (pinfunction "6_6") (pintype "passive"))
      (node (ref "R3") (pin "2") (pinfunction "2_2") (pintype "passive"))
      (node (ref "U4") (pin "3") (pinfunction "GPB2_3") (pintype "bidirectional"))
    )
    (net (code "83") (name "Net-(U4-GPB3)") (class "Default")
      (node (ref "JP5") (pin "5") (pinfunction "5_5") (pintype "passive"))
      (node (ref "R4") (pin "2") (pinfunction "2_2") (pintype "passive"))
      (node (ref "U4") (pin "4") (pinfunction "GPB3_4") (pintype "bidirectional"))
    )
    (net (code "84") (name "Net-(U4-GPB4)") (class "Default")
      (node (ref "JP5") (pin "4") (pinfunction "4_4") (pintype "passive"))
      (node (ref "R5") (pin "2") (pinfunction "2_2") (pintype "passive"))
      (node (ref "U4") (pin "5") (pinfunction "GPB4_5") (pintype "bidirectional"))
    )
    (net (code "85") (name "Net-(U4-GPB5)") (class "Default")
      (node (ref "JP5") (pin "3") (pinfunction "3_3") (pintype "passive"))
      (node (ref "R6") (pin "2") (pinfunction "2_2") (pintype "passive"))
      (node (ref "U4") (pin "6") (pinfunction "GPB5_6") (pintype "bidirectional"))
    )
    (net (code "86") (name "Net-(U4-GPB6)") (class "Default")
      (node (ref "JP5") (pin "2") (pinfunction "2_2") (pintype "passive"))
      (node (ref "R7") (pin "2") (pinfunction "2_2") (pintype "passive"))
      (node (ref "U4") (pin "7") (pinfunction "GPB6_7") (pintype "bidirectional"))
    )
    (net (code "87") (name "Net-(U4-GPB7)") (class "Default")
      (node (ref "JP5") (pin "1") (pinfunction "1_1") (pintype "passive"))
      (node (ref "R8") (pin "2") (pinfunction "2_2") (pintype "passive"))
      (node (ref "U4") (pin "8") (pinfunction "GPB7_8") (pintype "bidirectional"))
    )
    (net (code "88") (name "VCC") (class "Default")
      (node (ref "JP11") (pin "1") (pinfunction "1_1") (pintype "passive"))
      (node (ref "JP12") (pin "1") (pinfunction "1_1") (pintype "passive"))
      (node (ref "JP17") (pin "1") (pinfunction "1_1") (pintype "passive"))
      (node (ref "SJ1") (pin "3") (pinfunction "3_3") (pintype "passive"))
      (node (ref "SJ10") (pin "3") (pinfunction "3_3") (pintype "passive"))
      (node (ref "SJ11") (pin "3") (pinfunction "3_3") (pintype "passive"))
      (node (ref "SJ12") (pin "3") (pinfunction "3_3") (pintype "passive"))
      (node (ref "SJ2") (pin "3") (pinfunction "3_3") (pintype "passive"))
      (node (ref "SJ3") (pin "3") (pinfunction "3_3") (pintype "passive"))
      (node (ref "SJ4") (pin "3") (pinfunction "3_3") (pintype "passive"))
      (node (ref "SJ5") (pin "3") (pinfunction "3_3") (pintype "passive"))
      (node (ref "SJ6") (pin "3") (pinfunction "3_3") (pintype "passive"))
      (node (ref "SJ7") (pin "3") (pinfunction "3_3") (pintype "passive"))
      (node (ref "SJ8") (pin "3") (pinfunction "3_3") (pintype "passive"))
      (node (ref "SJ9") (pin "3") (pinfunction "3_3") (pintype "passive"))
      (node (ref "U1") (pin "18") (pinfunction "~{RESET}_18") (pintype "bidirectional"))
      (node (ref "U1") (pin "9") (pinfunction "VDD_9") (pintype "power_in"))
      (node (ref "U2") (pin "18") (pinfunction "~{RESET}_18") (pintype "bidirectional"))
      (node (ref "U2") (pin "9") (pinfunction "VDD_9") (pintype "power_in"))
      (node (ref "U3") (pin "18") (pinfunction "~{RESET}_18") (pintype "bidirectional"))
      (node (ref "U3") (pin "9") (pinfunction "VDD_9") (pintype "power_in"))
      (node (ref "U4") (pin "18") (pinfunction "~{RESET}_18") (pintype "bidirectional"))
      (node (ref "U4") (pin "9") (pinfunction "VDD_9") (pintype "power_in"))
    )
    (net (code "89") (name "unconnected-(U1-NC-Pad11)") (class "Default")
      (node (ref "U1") (pin "11") (pinfunction "NC_11") (pintype "no_connect"))
    )
    (net (code "90") (name "unconnected-(U1-NC-Pad14)") (class "Default")
      (node (ref "U1") (pin "14") (pinfunction "NC_14") (pintype "no_connect"))
    )
    (net (code "91") (name "unconnected-(U2-NC-Pad11)") (class "Default")
      (node (ref "U2") (pin "11") (pinfunction "NC_11") (pintype "no_connect"))
    )
    (net (code "92") (name "unconnected-(U2-NC-Pad14)") (class "Default")
      (node (ref "U2") (pin "14") (pinfunction "NC_14") (pintype "no_connect"))
    )
    (net (code "93") (name "unconnected-(U3-NC-Pad11)") (class "Default")
      (node (ref "U3") (pin "11") (pinfunction "NC_11") (pintype "no_connect"))
    )
    (net (code "94") (name "unconnected-(U3-NC-Pad14)") (class "Default")
      (node (ref "U3") (pin "14") (pinfunction "NC_14") (pintype "no_connect"))
    )
    (net (code "95") (name "unconnected-(U4-NC-Pad11)") (class "Default")
      (node (ref "U4") (pin "11") (pinfunction "NC_11") (pintype "no_connect"))
    )
    (net (code "96") (name "unconnected-(U4-NC-Pad14)") (class "Default")
      (node (ref "U4") (pin "14") (pinfunction "NC_14") (pintype "no_connect"))
    )
  )
)
